# video_kb.net
KiCad netlist of a schematic drawn in EAGLE
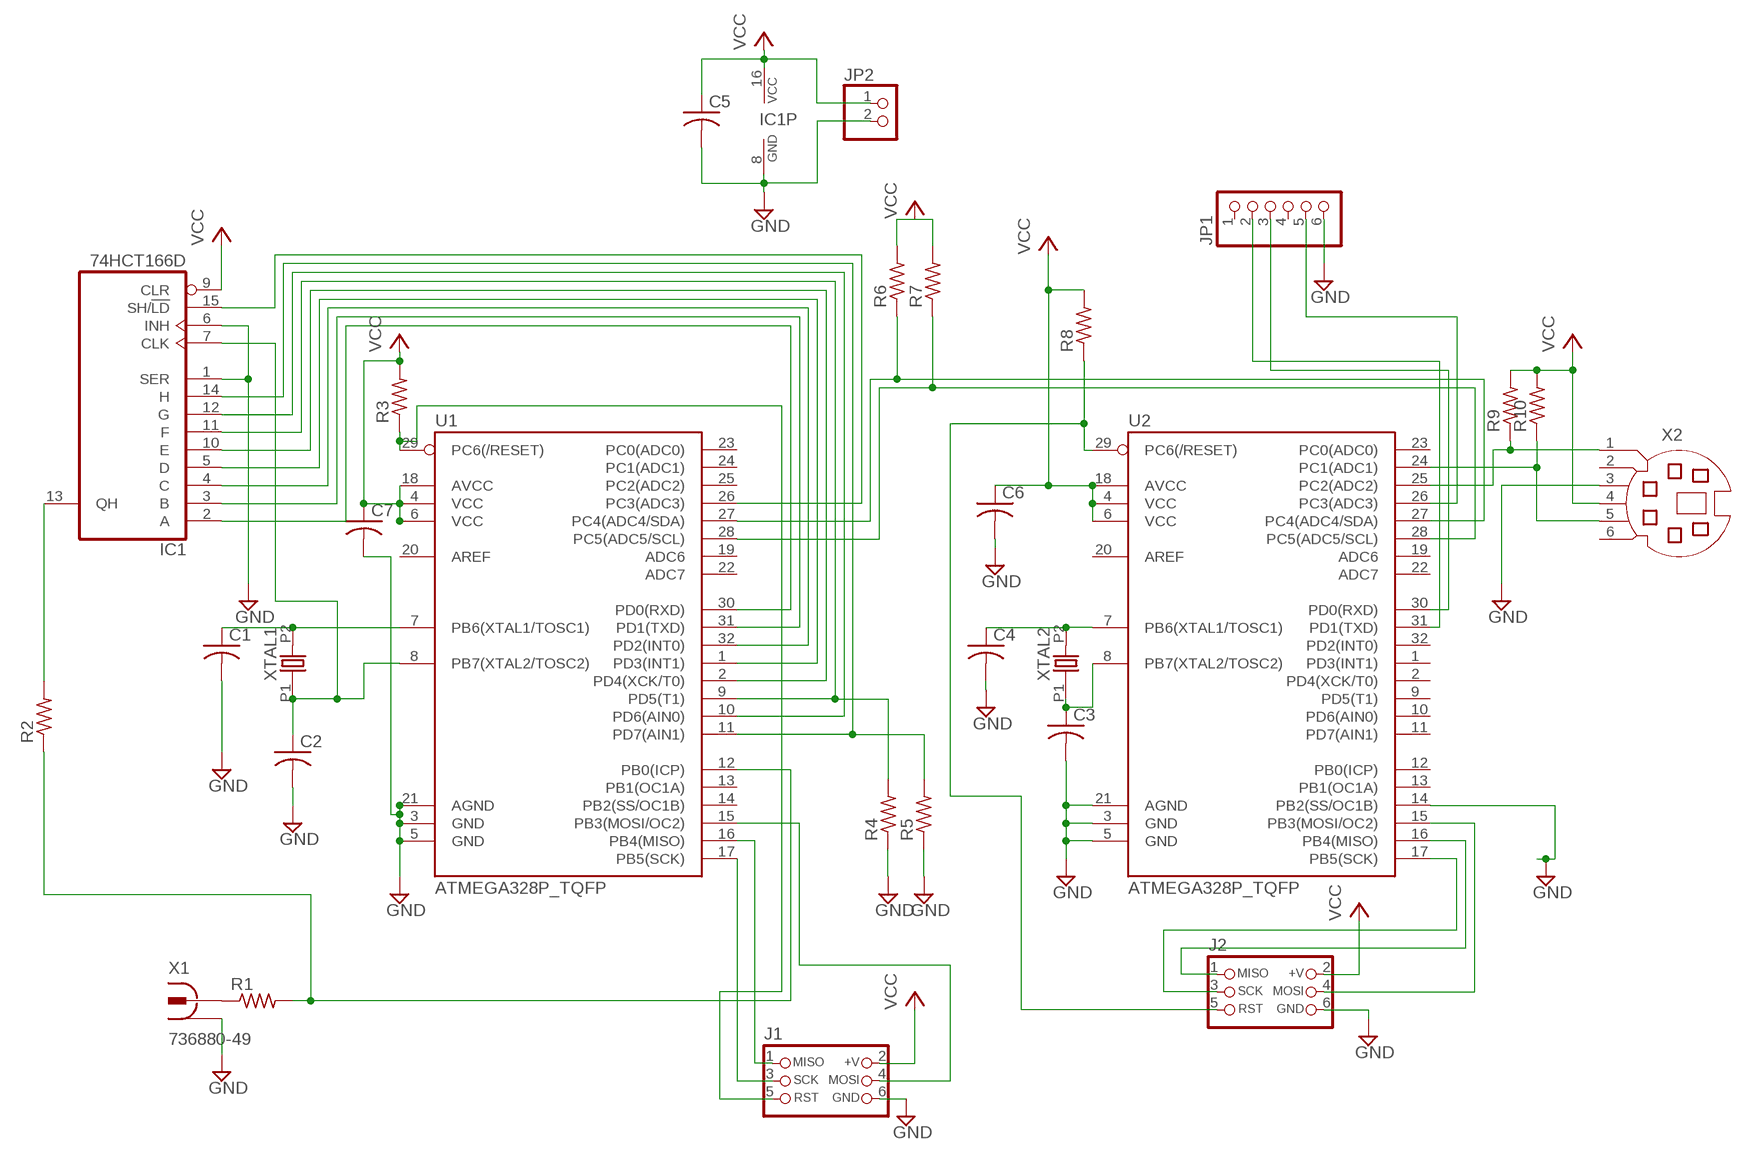
[diagram p0: schematic, sheet 1]

(export (version "E")
  (design (tool "Eeschema 10.0.6"))
  (components
    (comp (ref "C1")
      (value "C-USC0603K")
      (footprint "eagle-import:C0603K")
      (libsource (lib "eagle-import") (part "C-USC0603K"))
    )
    (comp (ref "C2")
      (value "C-USC0603K")
      (footprint "eagle-import:C0603K")
      (libsource (lib "eagle-import") (part "C-USC0603K"))
    )
    (comp (ref "C3")
      (value "C-USC0603K")
      (footprint "eagle-import:C0603K")
      (libsource (lib "eagle-import") (part "C-USC0603K"))
    )
    (comp (ref "C4")
      (value "C-USC0603K")
      (footprint "eagle-import:C0603K")
      (libsource (lib "eagle-import") (part "C-USC0603K"))
    )
    (comp (ref "C5")
      (value "C-USC0603K")
      (footprint "eagle-import:C0603K")
      (libsource (lib "eagle-import") (part "C-USC0603K"))
    )
    (comp (ref "C6")
      (value "C-USC0603K")
      (footprint "eagle-import:C0603K")
      (libsource (lib "eagle-import") (part "C-USC0603K"))
    )
    (comp (ref "C7")
      (value "C-USC0603K")
      (footprint "eagle-import:C0603K")
      (libsource (lib "eagle-import") (part "C-USC0603K"))
    )
    (comp (ref "IC1")
      (value "74HCT166D")
      (footprint "eagle-import:SO16")
      (libsource (lib "eagle-import") (part "74166DHCT"))
    )
    (comp (ref "J1")
      (value "CON_HEADER_PRG_AVR_ICSP-PTH")
      (footprint "eagle-import:HEADER_PRG_2X03")
      (libsource (lib "eagle-import") (part "CON_HEADER_PRG_AVR_ICSP-PTH"))
    )
    (comp (ref "J2")
      (value "CON_HEADER_PRG_AVR_ICSP-PTH")
      (footprint "eagle-import:HEADER_PRG_2X03")
      (libsource (lib "eagle-import") (part "CON_HEADER_PRG_AVR_ICSP-PTH"))
    )
    (comp (ref "JP1")
      (value "HEADER-1X6")
      (footprint "eagle-import:1X06_OVAL")
      (libsource (lib "eagle-import") (part "HEADER-1X6"))
    )
    (comp (ref "JP2")
      (value "HEADER-1X2")
      (footprint "eagle-import:1X02_OVAL")
      (libsource (lib "eagle-import") (part "HEADER-1X2"))
    )
    (comp (ref "R1")
      (value "R-US_R0603")
      (footprint "eagle-import:R0603")
      (libsource (lib "eagle-import") (part "R-US_R0603"))
    )
    (comp (ref "R2")
      (value "R-US_R0603")
      (footprint "eagle-import:R0603")
      (libsource (lib "eagle-import") (part "R-US_R0603"))
    )
    (comp (ref "R3")
      (value "R-US_R0603")
      (footprint "eagle-import:R0603")
      (libsource (lib "eagle-import") (part "R-US_R0603"))
    )
    (comp (ref "R4")
      (value "R-US_R0603")
      (footprint "eagle-import:R0603")
      (libsource (lib "eagle-import") (part "R-US_R0603"))
    )
    (comp (ref "R5")
      (value "R-US_R0603")
      (footprint "eagle-import:R0603")
      (libsource (lib "eagle-import") (part "R-US_R0603"))
    )
    (comp (ref "R6")
      (value "R-US_R0603")
      (footprint "eagle-import:R0603")
      (libsource (lib "eagle-import") (part "R-US_R0603"))
    )
    (comp (ref "R7")
      (value "R-US_R0603")
      (footprint "eagle-import:R0603")
      (libsource (lib "eagle-import") (part "R-US_R0603"))
    )
    (comp (ref "R8")
      (value "R-US_R0603")
      (footprint "eagle-import:R0603")
      (libsource (lib "eagle-import") (part "R-US_R0603"))
    )
    (comp (ref "R9")
      (value "R-US_R0603")
      (footprint "eagle-import:R0603")
      (libsource (lib "eagle-import") (part "R-US_R0603"))
    )
    (comp (ref "R10")
      (value "R-US_R0603")
      (footprint "eagle-import:R0603")
      (libsource (lib "eagle-import") (part "R-US_R0603"))
    )
    (comp (ref "U1")
      (value "ATMEGA328P_TQFP")
      (footprint "eagle-import:TQFP32-08")
      (libsource (lib "eagle-import") (part "ATMEGA328P_TQFP"))
    )
    (comp (ref "U2")
      (value "ATMEGA328P_TQFP")
      (footprint "eagle-import:TQFP32-08")
      (libsource (lib "eagle-import") (part "ATMEGA328P_TQFP"))
    )
    (comp (ref "X1")
      (value "736880-49")
      (footprint "eagle-import:736880-49")
      (libsource (lib "eagle-import") (part "736880-49"))
    )
    (comp (ref "X2")
      (value "MD06S")
      (footprint "eagle-import:MDIN06S")
      (libsource (lib "eagle-import") (part "MD06S"))
    )
    (comp (ref "XTAL1")
      (value "OSC-XTAL-HC-49U-PTH")
      (footprint "eagle-import:HC-49U-PTH")
      (libsource (lib "eagle-import") (part "OSC-XTAL-HC-49U-PTH"))
    )
    (comp (ref "XTAL2")
      (value "OSC-XTAL-HC-49U-PTH")
      (footprint "eagle-import:HC-49U-PTH")
      (libsource (lib "eagle-import") (part "OSC-XTAL-HC-49U-PTH"))
    )
  )
  (nets
    (net (code "1") (name "GND") (class "Default")
      (node (ref "C1") (pin "2") (pinfunction "2_2") (pintype "passive"))
      (node (ref "C2") (pin "2") (pinfunction "2_2") (pintype "passive"))
      (node (ref "C3") (pin "2") (pinfunction "2_2") (pintype "passive"))
      (node (ref "C4") (pin "2") (pinfunction "2_2") (pintype "passive"))
      (node (ref "C5") (pin "2") (pinfunction "2_2") (pintype "passive"))
      (node (ref "C6") (pin "2") (pinfunction "2_2") (pintype "passive"))
      (node (ref "C7") (pin "2") (pinfunction "2_2") (pintype "passive"))
      (node (ref "IC1") (pin "1") (pinfunction "SER_1") (pintype "input"))
      (node (ref "IC1") (pin "6") (pinfunction "INH_6") (pintype "input"))
      (node (ref "IC1") (pin "8") (pinfunction "GND_8") (pintype "power_in"))
      (node (ref "J1") (pin "6") (pinfunction "GND_6") (pintype "passive"))
      (node (ref "J2") (pin "6") (pinfunction "GND_6") (pintype "passive"))
      (node (ref "JP1") (pin "6") (pinfunction "6_6") (pintype "passive"))
      (node (ref "JP2") (pin "2") (pinfunction "2_2") (pintype "passive"))
      (node (ref "R4") (pin "1") (pinfunction "1_1") (pintype "passive"))
      (node (ref "R5") (pin "1") (pinfunction "1_1") (pintype "passive"))
      (node (ref "U1") (pin "21") (pinfunction "AGND_21") (pintype "bidirectional"))
      (node (ref "U1") (pin "3") (pinfunction "GND_3") (pintype "bidirectional"))
      (node (ref "U1") (pin "5") (pinfunction "GND_5") (pintype "bidirectional"))
      (node (ref "U2") (pin "14") (pinfunction "PB2(SS/OC1B)_14") (pintype "bidirectional"))
      (node (ref "U2") (pin "21") (pinfunction "AGND_21") (pintype "bidirectional"))
      (node (ref "U2") (pin "3") (pinfunction "GND_3") (pintype "bidirectional"))
      (node (ref "U2") (pin "5") (pinfunction "GND_5") (pintype "bidirectional"))
      (node (ref "X1") (pin "1") (pinfunction "1_1") (pintype "passive"))
      (node (ref "X1") (pin "1@1") (pinfunction "1_1@1") (pintype "passive"))
      (node (ref "X1") (pin "1@2") (pinfunction "1_1@2") (pintype "passive"))
      (node (ref "X2") (pin "3") (pinfunction "3_3") (pintype "passive"))
    )
    (net (code "2") (name "Net-(IC1A-A)") (class "Default")
      (node (ref "IC1") (pin "2") (pinfunction "A_2") (pintype "input"))
      (node (ref "U1") (pin "30") (pinfunction "PD0(RXD)_30") (pintype "bidirectional"))
    )
    (net (code "3") (name "Net-(IC1A-B)") (class "Default")
      (node (ref "IC1") (pin "3") (pinfunction "B_3") (pintype "input"))
      (node (ref "U1") (pin "31") (pinfunction "PD1(TXD)_31") (pintype "bidirectional"))
    )
    (net (code "4") (name "Net-(IC1A-C)") (class "Default")
      (node (ref "IC1") (pin "4") (pinfunction "C_4") (pintype "input"))
      (node (ref "U1") (pin "32") (pinfunction "PD2(INT0)_32") (pintype "bidirectional"))
    )
    (net (code "5") (name "Net-(IC1A-CLK)") (class "Default")
      (node (ref "C2") (pin "1") (pinfunction "1_1") (pintype "passive"))
      (node (ref "IC1") (pin "7") (pinfunction "CLK_7") (pintype "input"))
      (node (ref "U1") (pin "8") (pinfunction "PB7(XTAL2/TOSC2)_8") (pintype "bidirectional"))
      (node (ref "XTAL1") (pin "P1") (pinfunction "1_P1") (pintype "passive"))
    )
    (net (code "6") (name "Net-(IC1A-D)") (class "Default")
      (node (ref "IC1") (pin "5") (pinfunction "D_5") (pintype "input"))
      (node (ref "U1") (pin "1") (pinfunction "PD3(INT1)_1") (pintype "bidirectional"))
    )
    (net (code "7") (name "Net-(IC1A-E)") (class "Default")
      (node (ref "IC1") (pin "10") (pinfunction "E_10") (pintype "input"))
      (node (ref "U1") (pin "2") (pinfunction "PD4(XCK/T0)_2") (pintype "bidirectional"))
    )
    (net (code "8") (name "Net-(IC1A-F)") (class "Default")
      (node (ref "IC1") (pin "11") (pinfunction "F_11") (pintype "input"))
      (node (ref "R4") (pin "2") (pinfunction "2_2") (pintype "passive"))
      (node (ref "U1") (pin "9") (pinfunction "PD5(T1)_9") (pintype "bidirectional"))
    )
    (net (code "9") (name "Net-(IC1A-G)") (class "Default")
      (node (ref "IC1") (pin "12") (pinfunction "G_12") (pintype "input"))
      (node (ref "U1") (pin "10") (pinfunction "PD6(AIN0)_10") (pintype "bidirectional"))
    )
    (net (code "10") (name "Net-(IC1A-H)") (class "Default")
      (node (ref "IC1") (pin "14") (pinfunction "H_14") (pintype "input"))
      (node (ref "R5") (pin "2") (pinfunction "2_2") (pintype "passive"))
      (node (ref "U1") (pin "11") (pinfunction "PD7(AIN1)_11") (pintype "bidirectional"))
    )
    (net (code "11") (name "Net-(IC1A-QH)") (class "Default")
      (node (ref "IC1") (pin "13") (pinfunction "QH_13") (pintype "output"))
      (node (ref "R2") (pin "2") (pinfunction "2_2") (pintype "passive"))
    )
    (net (code "12") (name "Net-(IC1A-SH{slash}~{LD})") (class "Default")
      (node (ref "IC1") (pin "15") (pinfunction "SH/~{LD}_15") (pintype "input"))
      (node (ref "U1") (pin "26") (pinfunction "PC3(ADC3)_26") (pintype "bidirectional"))
    )
    (net (code "13") (name "Net-(J1-MISO)") (class "Default")
      (node (ref "J1") (pin "1") (pinfunction "MISO_1") (pintype "passive"))
      (node (ref "U1") (pin "16") (pinfunction "PB4(MISO)_16") (pintype "bidirectional"))
    )
    (net (code "14") (name "Net-(J1-MOSI)") (class "Default")
      (node (ref "J1") (pin "4") (pinfunction "MOSI_4") (pintype "passive"))
      (node (ref "U1") (pin "15") (pinfunction "PB3(MOSI/OC2)_15") (pintype "bidirectional"))
    )
    (net (code "15") (name "Net-(J1-RST)") (class "Default")
      (node (ref "J1") (pin "5") (pinfunction "RST_5") (pintype "passive"))
      (node (ref "R3") (pin "1") (pinfunction "1_1") (pintype "passive"))
      (node (ref "U1") (pin "29") (pinfunction "PC6(/RESET)_29") (pintype "bidirectional"))
    )
    (net (code "16") (name "Net-(J1-SCK)") (class "Default")
      (node (ref "J1") (pin "3") (pinfunction "SCK_3") (pintype "passive"))
      (node (ref "U1") (pin "17") (pinfunction "PB5(SCK)_17") (pintype "bidirectional"))
    )
    (net (code "17") (name "Net-(J2-MISO)") (class "Default")
      (node (ref "J2") (pin "1") (pinfunction "MISO_1") (pintype "passive"))
      (node (ref "U2") (pin "16") (pinfunction "PB4(MISO)_16") (pintype "bidirectional"))
    )
    (net (code "18") (name "Net-(J2-MOSI)") (class "Default")
      (node (ref "J2") (pin "4") (pinfunction "MOSI_4") (pintype "passive"))
      (node (ref "U2") (pin "15") (pinfunction "PB3(MOSI/OC2)_15") (pintype "bidirectional"))
    )
    (net (code "19") (name "Net-(J2-RST)") (class "Default")
      (node (ref "J2") (pin "5") (pinfunction "RST_5") (pintype "passive"))
      (node (ref "R8") (pin "1") (pinfunction "1_1") (pintype "passive"))
      (node (ref "U2") (pin "29") (pinfunction "PC6(/RESET)_29") (pintype "bidirectional"))
    )
    (net (code "20") (name "Net-(J2-SCK)") (class "Default")
      (node (ref "J2") (pin "3") (pinfunction "SCK_3") (pintype "passive"))
      (node (ref "U2") (pin "17") (pinfunction "PB5(SCK)_17") (pintype "bidirectional"))
    )
    (net (code "21") (name "Net-(R1-Pad1)") (class "Default")
      (node (ref "R1") (pin "1") (pinfunction "1_1") (pintype "passive"))
      (node (ref "X1") (pin "2") (pinfunction "2_2") (pintype "passive"))
    )
    (net (code "22") (name "Net-(U1-PB0(ICP))") (class "Default")
      (node (ref "R1") (pin "2") (pinfunction "2_2") (pintype "passive"))
      (node (ref "R2") (pin "1") (pinfunction "1_1") (pintype "passive"))
      (node (ref "U1") (pin "12") (pinfunction "PB0(ICP)_12") (pintype "bidirectional"))
    )
    (net (code "23") (name "Net-(U1-PB6(XTAL1{slash}TOSC1))") (class "Default")
      (node (ref "C1") (pin "1") (pinfunction "1_1") (pintype "passive"))
      (node (ref "U1") (pin "7") (pinfunction "PB6(XTAL1/TOSC1)_7") (pintype "bidirectional"))
      (node (ref "XTAL1") (pin "P2") (pinfunction "2_P2") (pintype "passive"))
    )
    (net (code "24") (name "Net-(U1-PC4(ADC4{slash}SDA))") (class "Default")
      (node (ref "R6") (pin "1") (pinfunction "1_1") (pintype "passive"))
      (node (ref "U1") (pin "27") (pinfunction "PC4(ADC4/SDA)_27") (pintype "bidirectional"))
      (node (ref "U2") (pin "27") (pinfunction "PC4(ADC4/SDA)_27") (pintype "bidirectional"))
    )
    (net (code "25") (name "Net-(U1-PC5(ADC5{slash}SCL))") (class "Default")
      (node (ref "R7") (pin "1") (pinfunction "1_1") (pintype "passive"))
      (node (ref "U1") (pin "28") (pinfunction "PC5(ADC5/SCL)_28") (pintype "bidirectional"))
      (node (ref "U2") (pin "28") (pinfunction "PC5(ADC5/SCL)_28") (pintype "bidirectional"))
    )
    (net (code "26") (name "Net-(U2-PB6(XTAL1{slash}TOSC1))") (class "Default")
      (node (ref "C4") (pin "1") (pinfunction "1_1") (pintype "passive"))
      (node (ref "U2") (pin "7") (pinfunction "PB6(XTAL1/TOSC1)_7") (pintype "bidirectional"))
      (node (ref "XTAL2") (pin "P2") (pinfunction "2_P2") (pintype "passive"))
    )
    (net (code "27") (name "Net-(U2-PB7(XTAL2{slash}TOSC2))") (class "Default")
      (node (ref "C3") (pin "1") (pinfunction "1_1") (pintype "passive"))
      (node (ref "U2") (pin "8") (pinfunction "PB7(XTAL2/TOSC2)_8") (pintype "bidirectional"))
      (node (ref "XTAL2") (pin "P1") (pinfunction "1_P1") (pintype "passive"))
    )
    (net (code "28") (name "Net-(U2-PC1(ADC1))") (class "Default")
      (node (ref "R10") (pin "1") (pinfunction "1_1") (pintype "passive"))
      (node (ref "U2") (pin "24") (pinfunction "PC1(ADC1)_24") (pintype "bidirectional"))
      (node (ref "X2") (pin "5") (pinfunction "5_5") (pintype "passive"))
    )
    (net (code "29") (name "Net-(U2-PC2(ADC2))") (class "Default")
      (node (ref "R9") (pin "1") (pinfunction "1_1") (pintype "passive"))
      (node (ref "U2") (pin "25") (pinfunction "PC2(ADC2)_25") (pintype "bidirectional"))
      (node (ref "X2") (pin "1") (pinfunction "1_1") (pintype "passive"))
    )
    (net (code "30") (name "Net-(U2-PC3(ADC3))") (class "Default")
      (node (ref "JP1") (pin "5") (pinfunction "5_5") (pintype "passive"))
      (node (ref "U2") (pin "26") (pinfunction "PC3(ADC3)_26") (pintype "bidirectional"))
    )
    (net (code "31") (name "Net-(U2-PD0(RXD))") (class "Default")
      (node (ref "JP1") (pin "3") (pinfunction "3_3") (pintype "passive"))
      (node (ref "U2") (pin "30") (pinfunction "PD0(RXD)_30") (pintype "bidirectional"))
    )
    (net (code "32") (name "Net-(U2-PD1(TXD))") (class "Default")
      (node (ref "JP1") (pin "2") (pinfunction "2_2") (pintype "passive"))
      (node (ref "U2") (pin "31") (pinfunction "PD1(TXD)_31") (pintype "bidirectional"))
    )
    (net (code "33") (name "VCC") (class "Default")
      (node (ref "C5") (pin "1") (pinfunction "1_1") (pintype "passive"))
      (node (ref "C6") (pin "1") (pinfunction "1_1") (pintype "passive"))
      (node (ref "C7") (pin "1") (pinfunction "1_1") (pintype "passive"))
      (node (ref "IC1") (pin "16") (pinfunction "VCC_16") (pintype "power_in"))
      (node (ref "IC1") (pin "9") (pinfunction "CLR_9") (pintype "input"))
      (node (ref "J1") (pin "2") (pinfunction "+V_2") (pintype "passive"))
      (node (ref "J2") (pin "2") (pinfunction "+V_2") (pintype "passive"))
      (node (ref "JP2") (pin "1") (pinfunction "1_1") (pintype "passive"))
      (node (ref "R10") (pin "2") (pinfunction "2_2") (pintype "passive"))
      (node (ref "R3") (pin "2") (pinfunction "2_2") (pintype "passive"))
      (node (ref "R6") (pin "2") (pinfunction "2_2") (pintype "passive"))
      (node (ref "R7") (pin "2") (pinfunction "2_2") (pintype "passive"))
      (node (ref "R8") (pin "2") (pinfunction "2_2") (pintype "passive"))
      (node (ref "R9") (pin "2") (pinfunction "2_2") (pintype "passive"))
      (node (ref "U1") (pin "18") (pinfunction "AVCC_18") (pintype "bidirectional"))
      (node (ref "U1") (pin "4") (pinfunction "VCC_4") (pintype "bidirectional"))
      (node (ref "U1") (pin "6") (pinfunction "VCC_6") (pintype "bidirectional"))
      (node (ref "U2") (pin "18") (pinfunction "AVCC_18") (pintype "bidirectional"))
      (node (ref "U2") (pin "4") (pinfunction "VCC_4") (pintype "bidirectional"))
      (node (ref "U2") (pin "6") (pinfunction "VCC_6") (pintype "bidirectional"))
      (node (ref "X2") (pin "4") (pinfunction "4_4") (pintype "passive"))
    )
    (net (code "34") (name "unconnected-(JP1-Pad1)") (class "Default")
      (node (ref "JP1") (pin "1") (pinfunction "1_1") (pintype "passive"))
    )
    (net (code "35") (name "unconnected-(JP1-Pad4)") (class "Default")
      (node (ref "JP1") (pin "4") (pinfunction "4_4") (pintype "passive"))
    )
    (net (code "36") (name "unconnected-(U1-ADC6-Pad19)") (class "Default")
      (node (ref "U1") (pin "19") (pinfunction "ADC6_19") (pintype "bidirectional"))
    )
    (net (code "37") (name "unconnected-(U1-ADC7-Pad22)") (class "Default")
      (node (ref "U1") (pin "22") (pinfunction "ADC7_22") (pintype "bidirectional"))
    )
    (net (code "38") (name "unconnected-(U1-AREF-Pad20)") (class "Default")
      (node (ref "U1") (pin "20") (pinfunction "AREF_20") (pintype "bidirectional"))
    )
    (net (code "39") (name "unconnected-(U1-PB1(OC1A)-Pad13)") (class "Default")
      (node (ref "U1") (pin "13") (pinfunction "PB1(OC1A)_13") (pintype "bidirectional"))
    )
    (net (code "40") (name "unconnected-(U1-PB2(SS{slash}OC1B)-Pad14)") (class "Default")
      (node (ref "U1") (pin "14") (pinfunction "PB2(SS/OC1B)_14") (pintype "bidirectional"))
    )
    (net (code "41") (name "unconnected-(U1-PC0(ADC0)-Pad23)") (class "Default")
      (node (ref "U1") (pin "23") (pinfunction "PC0(ADC0)_23") (pintype "bidirectional"))
    )
    (net (code "42") (name "unconnected-(U1-PC1(ADC1)-Pad24)") (class "Default")
      (node (ref "U1") (pin "24") (pinfunction "PC1(ADC1)_24") (pintype "bidirectional"))
    )
    (net (code "43") (name "unconnected-(U1-PC2(ADC2)-Pad25)") (class "Default")
      (node (ref "U1") (pin "25") (pinfunction "PC2(ADC2)_25") (pintype "bidirectional"))
    )
    (net (code "44") (name "unconnected-(U2-ADC6-Pad19)") (class "Default")
      (node (ref "U2") (pin "19") (pinfunction "ADC6_19") (pintype "bidirectional"))
    )
    (net (code "45") (name "unconnected-(U2-ADC7-Pad22)") (class "Default")
      (node (ref "U2") (pin "22") (pinfunction "ADC7_22") (pintype "bidirectional"))
    )
    (net (code "46") (name "unconnected-(U2-AREF-Pad20)") (class "Default")
      (node (ref "U2") (pin "20") (pinfunction "AREF_20") (pintype "bidirectional"))
    )
    (net (code "47") (name "unconnected-(U2-PB0(ICP)-Pad12)") (class "Default")
      (node (ref "U2") (pin "12") (pinfunction "PB0(ICP)_12") (pintype "bidirectional"))
    )
    (net (code "48") (name "unconnected-(U2-PB1(OC1A)-Pad13)") (class "Default")
      (node (ref "U2") (pin "13") (pinfunction "PB1(OC1A)_13") (pintype "bidirectional"))
    )
    (net (code "49") (name "unconnected-(U2-PC0(ADC0)-Pad23)") (class "Default")
      (node (ref "U2") (pin "23") (pinfunction "PC0(ADC0)_23") (pintype "bidirectional"))
    )
    (net (code "50") (name "unconnected-(U2-PD2(INT0)-Pad32)") (class "Default")
      (node (ref "U2") (pin "32") (pinfunction "PD2(INT0)_32") (pintype "bidirectional"))
    )
    (net (code "51") (name "unconnected-(U2-PD3(INT1)-Pad1)") (class "Default")
      (node (ref "U2") (pin "1") (pinfunction "PD3(INT1)_1") (pintype "bidirectional"))
    )
    (net (code "52") (name "unconnected-(U2-PD4(XCK{slash}T0)-Pad2)") (class "Default")
      (node (ref "U2") (pin "2") (pinfunction "PD4(XCK/T0)_2") (pintype "bidirectional"))
    )
    (net (code "53") (name "unconnected-(U2-PD5(T1)-Pad9)") (class "Default")
      (node (ref "U2") (pin "9") (pinfunction "PD5(T1)_9") (pintype "bidirectional"))
    )
    (net (code "54") (name "unconnected-(U2-PD6(AIN0)-Pad10)") (class "Default")
      (node (ref "U2") (pin "10") (pinfunction "PD6(AIN0)_10") (pintype "bidirectional"))
    )
    (net (code "55") (name "unconnected-(U2-PD7(AIN1)-Pad11)") (class "Default")
      (node (ref "U2") (pin "11") (pinfunction "PD7(AIN1)_11") (pintype "bidirectional"))
    )
    (net (code "56") (name "unconnected-(X2-Pad2)") (class "Default")
      (node (ref "X2") (pin "2") (pinfunction "2_2") (pintype "passive"))
    )
    (net (code "57") (name "unconnected-(X2-Pad6)") (class "Default")
      (node (ref "X2") (pin "6") (pinfunction "6_6") (pintype "passive"))
    )
  )
)
